# coqui-v1_0-linear.net
KiCad netlist of a schematic drawn in EAGLE
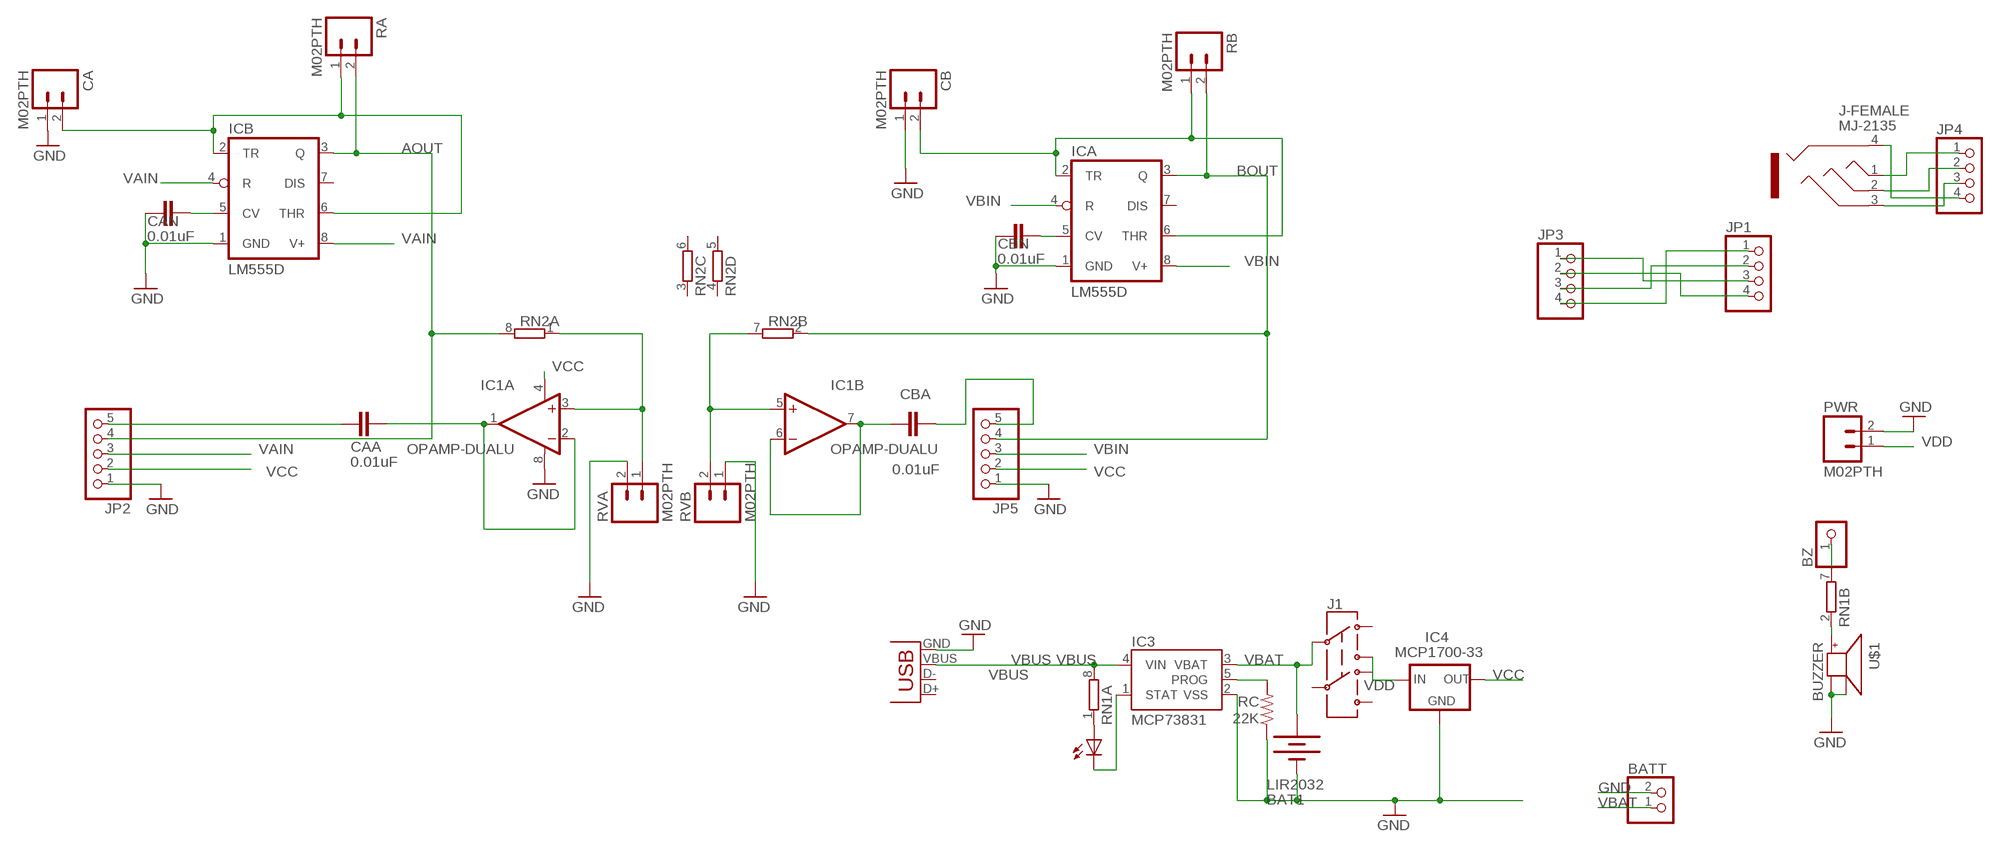
[diagram p0: schematic, sheet 1]

(export (version "E")
  (design (tool "Eeschema 10.0.6"))
  (components
    (comp (ref "BAT1")
      (value "LIR2032")
      (footprint "eagle-import:BATTCOM_20MM_PTH_SMT")
      (libsource (lib "eagle-import") (part "BATTERYBATTCOM_20MM_PTH_SMT"))
    )
    (comp (ref "BATT")
      (value "JST_2PIN-SMT-RA")
      (footprint "eagle-import:JST-PH-2-SMT-RA")
      (libsource (lib "eagle-import") (part "JST_2PIN-SMT-RA"))
    )
    (comp (ref "BZ")
      (value "PINHD-1X1")
      (footprint "eagle-import:1X01")
      (libsource (lib "eagle-import") (part "PINHD-1X1"))
    )
    (comp (ref "CA")
      (value "M02PTH")
      (footprint "eagle-import:1X02")
      (libsource (lib "eagle-import") (part "M02PTH"))
    )
    (comp (ref "CAA")
      (value "0.01uF")
      (footprint "eagle-import:C0805@1")
      (libsource (lib "eagle-import") (part "C-EUC0805"))
    )
    (comp (ref "CAN")
      (value "0.01uF")
      (footprint "eagle-import:C0805@1")
      (libsource (lib "eagle-import") (part "C-EUC0805"))
    )
    (comp (ref "CB")
      (value "M02PTH")
      (footprint "eagle-import:1X02")
      (libsource (lib "eagle-import") (part "M02PTH"))
    )
    (comp (ref "CBA")
      (value "0.01uF")
      (footprint "eagle-import:C0805@1")
      (libsource (lib "eagle-import") (part "C-EUC0805"))
    )
    (comp (ref "CBN")
      (value "0.01uF")
      (footprint "eagle-import:C0805@1")
      (libsource (lib "eagle-import") (part "C-EUC0805"))
    )
    (comp (ref "CHG")
      (value "0805")
      (footprint "eagle-import:CHIPLED_0805")
      (libsource (lib "eagle-import") (part "LEDCHIPLED_0805"))
    )
    (comp (ref "IC1")
      (value "OPAMP-DUALU")
      (footprint "eagle-import:SO08")
      (libsource (lib "eagle-import") (part "OPAMP-DUALU"))
    )
    (comp (ref "IC3")
      (value "MCP73831")
      (footprint "eagle-import:SOT23-5")
      (libsource (lib "eagle-import") (part "MCP73831"))
    )
    (comp (ref "IC4")
      (value "MCP1700-33")
      (footprint "eagle-import:SOT89")
      (libsource (lib "eagle-import") (part "MCP1700SOT89"))
    )
    (comp (ref "ICA")
      (value "LM555D")
      (footprint "eagle-import:SO08")
      (libsource (lib "eagle-import") (part "555DLM"))
    )
    (comp (ref "ICB")
      (value "LM555D")
      (footprint "eagle-import:SO08")
      (libsource (lib "eagle-import") (part "555DLM"))
    )
    (comp (ref "J-FEMALE")
      (value "MJ-2135")
      (footprint "eagle-import:MJ-2135")
      (libsource (lib "eagle-import") (part "MJ-2135"))
    )
    (comp (ref "J1")
      (value "AYZ0202")
      (footprint "eagle-import:AYZ0202")
      (libsource (lib "eagle-import") (part "AYZ0202"))
    )
    (comp (ref "JP1")
      (value "PINHD-1X4/90")
      (footprint "eagle-import:1X04_90")
      (libsource (lib "eagle-import") (part "trrs-dwb_PINHD-1X4/90"))
    )
    (comp (ref "JP2")
      (value "PINHD-1X5")
      (footprint "eagle-import:1X05")
      (libsource (lib "eagle-import") (part "PINHD-1X5"))
    )
    (comp (ref "JP3")
      (value "PINHD-1X4")
      (footprint "eagle-import:1X04")
      (libsource (lib "eagle-import") (part "PINHD-1X4"))
    )
    (comp (ref "JP4")
      (value "PINHD-1X4")
      (footprint "eagle-import:1X04")
      (libsource (lib "eagle-import") (part "PINHD-1X4"))
    )
    (comp (ref "JP5")
      (value "PINHD-1X5")
      (footprint "eagle-import:1X05")
      (libsource (lib "eagle-import") (part "PINHD-1X5"))
    )
    (comp (ref "PWR")
      (value "M02PTH")
      (footprint "eagle-import:1X02")
      (libsource (lib "eagle-import") (part "M02PTH"))
    )
    (comp (ref "RA")
      (value "M02PTH")
      (footprint "eagle-import:1X02")
      (libsource (lib "eagle-import") (part "M02PTH"))
    )
    (comp (ref "RB")
      (value "M02PTH")
      (footprint "eagle-import:1X02")
      (libsource (lib "eagle-import") (part "M02PTH"))
    )
    (comp (ref "RC")
      (value "22K")
      (footprint "eagle-import:R0805")
      (libsource (lib "eagle-import") (part "R-US_R0805"))
    )
    (comp (ref "RN1")
      (value "4R-NEXB38V")
      (footprint "eagle-import:EXB38V")
      (libsource (lib "eagle-import") (part "4R-NEXB38V"))
    )
    (comp (ref "RN2")
      (value "4R-NEXB38V")
      (footprint "eagle-import:EXB38V")
      (libsource (lib "eagle-import") (part "4R-NEXB38V"))
    )
    (comp (ref "RVA")
      (value "M02PTH")
      (footprint "eagle-import:1X02")
      (libsource (lib "eagle-import") (part "M02PTH"))
    )
    (comp (ref "RVB")
      (value "M02PTH")
      (footprint "eagle-import:1X02")
      (libsource (lib "eagle-import") (part "M02PTH"))
    )
    (comp (ref "U$1")
      (value "BUZZER")
      (footprint "eagle-import:SMT-8585-BUZZER")
      (libsource (lib "eagle-import") (part "BUZZER"))
    )
    (comp (ref "X1")
      (value "USBSMD")
      (footprint "eagle-import:USB-MINIB")
      (libsource (lib "eagle-import") (part "USBSMD"))
    )
  )
  (nets
    (net (code "1") (name "/AOUT") (class "Default")
      (node (ref "ICB") (pin "3") (pinfunction "Q_3") (pintype "output"))
      (node (ref "JP2") (pin "4") (pinfunction "4_4") (pintype "passive"))
      (node (ref "RA") (pin "2") (pinfunction "2_2") (pintype "passive"))
      (node (ref "RN2") (pin "8") (pinfunction "2_8") (pintype "passive"))
    )
    (net (code "2") (name "/BOUT") (class "Default")
      (node (ref "ICA") (pin "3") (pinfunction "Q_3") (pintype "output"))
      (node (ref "JP5") (pin "4") (pinfunction "4_4") (pintype "passive"))
      (node (ref "RB") (pin "2") (pinfunction "2_2") (pintype "passive"))
      (node (ref "RN2") (pin "2") (pinfunction "1_2") (pintype "passive"))
    )
    (net (code "3") (name "/N$23") (class "Default")
      (node (ref "IC1") (pin "3") (pinfunction "+IN_3") (pintype "input"))
      (node (ref "IC1") (pin "5") (pinfunction "+IN_5") (pintype "input"))
      (node (ref "RN2") (pin "1") (pinfunction "1_1") (pintype "passive"))
      (node (ref "RN2") (pin "7") (pinfunction "2_7") (pintype "passive"))
      (node (ref "RVA") (pin "1") (pinfunction "1_1") (pintype "passive"))
      (node (ref "RVB") (pin "2") (pinfunction "2_2") (pintype "passive"))
    )
    (net (code "4") (name "/VAIN") (class "Default")
      (node (ref "ICB") (pin "4") (pinfunction "R_4") (pintype "input"))
      (node (ref "ICB") (pin "8") (pinfunction "V+_8") (pintype "power_in"))
      (node (ref "JP2") (pin "3") (pinfunction "3_3") (pintype "passive"))
    )
    (net (code "5") (name "/VBAT") (class "Default")
      (node (ref "BAT1") (pin "P$2") (pinfunction "+_P$2") (pintype "power_in"))
      (node (ref "BATT") (pin "1") (pinfunction "2_1") (pintype "passive"))
      (node (ref "IC3") (pin "3") (pinfunction "VBAT_3") (pintype "power_in"))
      (node (ref "J1") (pin "2") (pinfunction "2_2") (pintype "bidirectional"))
    )
    (net (code "6") (name "/VBIN") (class "Default")
      (node (ref "ICA") (pin "4") (pinfunction "R_4") (pintype "input"))
      (node (ref "ICA") (pin "8") (pinfunction "V+_8") (pintype "power_in"))
      (node (ref "JP5") (pin "3") (pinfunction "3_3") (pintype "passive"))
    )
    (net (code "7") (name "/VBUS") (class "Default")
      (node (ref "IC3") (pin "4") (pinfunction "VIN_4") (pintype "power_in"))
      (node (ref "RN1") (pin "8") (pinfunction "2_8") (pintype "passive"))
      (node (ref "X1") (pin "VBUS") (pinfunction "VBUS_VBUS") (pintype "bidirectional"))
    )
    (net (code "8") (name "/VCC") (class "Default")
      (node (ref "IC1") (pin "4") (pinfunction "V-_4") (pintype "power_in"))
      (node (ref "IC4") (pin "3") (pinfunction "OUT_3") (pintype "passive"))
      (node (ref "JP2") (pin "2") (pinfunction "2_2") (pintype "passive"))
      (node (ref "JP5") (pin "2") (pinfunction "2_2") (pintype "passive"))
    )
    (net (code "9") (name "/VDD") (class "Default")
      (node (ref "IC4") (pin "2") (pinfunction "IN_2") (pintype "input"))
      (node (ref "J1") (pin "1") (pinfunction "3_1") (pintype "bidirectional"))
      (node (ref "PWR") (pin "1") (pinfunction "1_1") (pintype "passive"))
    )
    (net (code "10") (name "GND") (class "Default")
      (node (ref "BAT1") (pin "P$1") (pinfunction "-_P$1") (pintype "power_in"))
      (node (ref "BATT") (pin "2") (pinfunction "1_2") (pintype "passive"))
      (node (ref "CA") (pin "1") (pinfunction "1_1") (pintype "passive"))
      (node (ref "CAN") (pin "1") (pinfunction "1_1") (pintype "passive"))
      (node (ref "CB") (pin "1") (pinfunction "1_1") (pintype "passive"))
      (node (ref "CBN") (pin "1") (pinfunction "1_1") (pintype "passive"))
      (node (ref "IC1") (pin "8") (pinfunction "V+_8") (pintype "power_in"))
      (node (ref "IC3") (pin "2") (pinfunction "VSS_2") (pintype "power_in"))
      (node (ref "IC4") (pin "1") (pinfunction "GND_1") (pintype "input"))
      (node (ref "ICA") (pin "1") (pinfunction "GND_1") (pintype "power_in"))
      (node (ref "ICB") (pin "1") (pinfunction "GND_1") (pintype "power_in"))
      (node (ref "JP2") (pin "1") (pinfunction "1_1") (pintype "passive"))
      (node (ref "JP5") (pin "1") (pinfunction "1_1") (pintype "passive"))
      (node (ref "PWR") (pin "2") (pinfunction "2_2") (pintype "passive"))
      (node (ref "RC") (pin "1") (pinfunction "1_1") (pintype "passive"))
      (node (ref "RVA") (pin "2") (pinfunction "2_2") (pintype "passive"))
      (node (ref "RVB") (pin "1") (pinfunction "1_1") (pintype "passive"))
      (node (ref "U$1") (pin "-") (pinfunction "-_-") (pintype "passive"))
      (node (ref "U$1") (pin "A-") (pinfunction "A-_A-") (pintype "passive"))
      (node (ref "X1") (pin "GND") (pinfunction "GND_GND") (pintype "bidirectional"))
    )
    (net (code "11") (name "Net-(CAA-Pad1)") (class "Default")
      (node (ref "CAA") (pin "1") (pinfunction "1_1") (pintype "passive"))
      (node (ref "JP2") (pin "5") (pinfunction "5_5") (pintype "passive"))
    )
    (net (code "12") (name "Net-(CBA-Pad2)") (class "Default")
      (node (ref "CBA") (pin "2") (pinfunction "2_2") (pintype "passive"))
      (node (ref "JP5") (pin "5") (pinfunction "5_5") (pintype "passive"))
    )
    (net (code "13") (name "Net-(CHG-PadA)") (class "Default")
      (node (ref "CHG") (pin "A") (pinfunction "A_A") (pintype "passive"))
      (node (ref "RN1") (pin "1") (pinfunction "1_1") (pintype "passive"))
    )
    (net (code "14") (name "Net-(IC1A--IN)") (class "Default")
      (node (ref "CAA") (pin "2") (pinfunction "2_2") (pintype "passive"))
      (node (ref "IC1") (pin "1") (pinfunction "OUT_1") (pintype "output"))
      (node (ref "IC1") (pin "2") (pinfunction "-IN_2") (pintype "input"))
    )
    (net (code "15") (name "Net-(IC1B--IN)") (class "Default")
      (node (ref "CBA") (pin "1") (pinfunction "1_1") (pintype "passive"))
      (node (ref "IC1") (pin "6") (pinfunction "-IN_6") (pintype "input"))
      (node (ref "IC1") (pin "7") (pinfunction "OUT_7") (pintype "output"))
    )
    (net (code "16") (name "Net-(IC3-PROG)") (class "Default")
      (node (ref "IC3") (pin "5") (pinfunction "PROG_5") (pintype "input"))
      (node (ref "RC") (pin "2") (pinfunction "2_2") (pintype "passive"))
    )
    (net (code "17") (name "Net-(IC3-STAT)") (class "Default")
      (node (ref "CHG") (pin "C") (pinfunction "C_C") (pintype "passive"))
      (node (ref "IC3") (pin "1") (pinfunction "STAT_1") (pintype "output"))
    )
    (net (code "18") (name "Net-(ICA-CV)") (class "Default")
      (node (ref "CBN") (pin "2") (pinfunction "2_2") (pintype "passive"))
      (node (ref "ICA") (pin "5") (pinfunction "CV_5") (pintype "input"))
    )
    (net (code "19") (name "Net-(ICA-THR)") (class "Default")
      (node (ref "CB") (pin "2") (pinfunction "2_2") (pintype "passive"))
      (node (ref "ICA") (pin "2") (pinfunction "TR_2") (pintype "input"))
      (node (ref "ICA") (pin "6") (pinfunction "THR_6") (pintype "input"))
      (node (ref "RB") (pin "1") (pinfunction "1_1") (pintype "passive"))
    )
    (net (code "20") (name "Net-(ICB-CV)") (class "Default")
      (node (ref "CAN") (pin "2") (pinfunction "2_2") (pintype "passive"))
      (node (ref "ICB") (pin "5") (pinfunction "CV_5") (pintype "input"))
    )
    (net (code "21") (name "Net-(ICB-THR)") (class "Default")
      (node (ref "CA") (pin "2") (pinfunction "2_2") (pintype "passive"))
      (node (ref "ICB") (pin "2") (pinfunction "TR_2") (pintype "input"))
      (node (ref "ICB") (pin "6") (pinfunction "THR_6") (pintype "input"))
      (node (ref "RA") (pin "1") (pinfunction "1_1") (pintype "passive"))
    )
    (net (code "22") (name "Net-(J-FEMALE-Pad1)") (class "Default")
      (node (ref "J-FEMALE") (pin "1") (pinfunction "1_1") (pintype "passive"))
      (node (ref "JP4") (pin "1") (pinfunction "1_1") (pintype "passive"))
    )
    (net (code "23") (name "Net-(J-FEMALE-Pad2)") (class "Default")
      (node (ref "J-FEMALE") (pin "2") (pinfunction "2_2") (pintype "passive"))
      (node (ref "JP4") (pin "2") (pinfunction "2_2") (pintype "passive"))
    )
    (net (code "24") (name "Net-(J-FEMALE-Pad3)") (class "Default")
      (node (ref "J-FEMALE") (pin "3") (pinfunction "3_3") (pintype "passive"))
      (node (ref "JP4") (pin "3") (pinfunction "3_3") (pintype "passive"))
    )
    (net (code "25") (name "Net-(J-FEMALE-Pad4)") (class "Default")
      (node (ref "J-FEMALE") (pin "4") (pinfunction "4_4") (pintype "passive"))
      (node (ref "JP4") (pin "4") (pinfunction "4_4") (pintype "passive"))
    )
    (net (code "26") (name "Net-(JP1-Pad1)") (class "Default")
      (node (ref "JP1") (pin "1") (pinfunction "1_1") (pintype "passive"))
      (node (ref "JP3") (pin "4") (pinfunction "4_4") (pintype "passive"))
    )
    (net (code "27") (name "Net-(JP1-Pad2)") (class "Default")
      (node (ref "JP1") (pin "2") (pinfunction "2_2") (pintype "passive"))
      (node (ref "JP3") (pin "3") (pinfunction "3_3") (pintype "passive"))
    )
    (net (code "28") (name "Net-(JP1-Pad3)") (class "Default")
      (node (ref "JP1") (pin "3") (pinfunction "3_3") (pintype "passive"))
      (node (ref "JP3") (pin "1") (pinfunction "1_1") (pintype "passive"))
    )
    (net (code "29") (name "Net-(JP1-Pad4)") (class "Default")
      (node (ref "JP1") (pin "4") (pinfunction "4_4") (pintype "passive"))
      (node (ref "JP3") (pin "2") (pinfunction "2_2") (pintype "passive"))
    )
    (net (code "30") (name "Net-(RN1B-1)") (class "Default")
      (node (ref "RN1") (pin "2") (pinfunction "1_2") (pintype "passive"))
      (node (ref "U$1") (pin "+") (pinfunction "+_+") (pintype "passive"))
    )
    (net (code "31") (name "Net-(RN1B-2)") (class "Default")
      (node (ref "BZ") (pin "1") (pinfunction "1_1") (pintype "passive"))
      (node (ref "RN1") (pin "7") (pinfunction "2_7") (pintype "passive"))
    )
    (net (code "32") (name "unconnected-(ICA-DIS-Pad7)") (class "Default")
      (node (ref "ICA") (pin "7") (pinfunction "DIS_7") (pintype "input"))
    )
    (net (code "33") (name "unconnected-(ICB-DIS-Pad7)") (class "Default")
      (node (ref "ICB") (pin "7") (pinfunction "DIS_7") (pintype "input"))
    )
    (net (code "34") (name "unconnected-(J1-1-Pad3)") (class "Default")
      (node (ref "J1") (pin "3") (pinfunction "1_3") (pintype "bidirectional"))
    )
    (net (code "35") (name "unconnected-(J1-4-Pad6)") (class "Default")
      (node (ref "J1") (pin "6") (pinfunction "4_6") (pintype "bidirectional"))
    )
    (net (code "36") (name "unconnected-(J1-6-Pad4)") (class "Default")
      (node (ref "J1") (pin "4") (pinfunction "6_4") (pintype "bidirectional"))
    )
    (net (code "37") (name "unconnected-(J1-Pad5)") (class "Default")
      (node (ref "J1") (pin "5") (pinfunction "5_5") (pintype "bidirectional"))
    )
    (net (code "38") (name "unconnected-(RN2C-1-Pad3)") (class "Default")
      (node (ref "RN2") (pin "3") (pinfunction "1_3") (pintype "passive"))
    )
    (net (code "39") (name "unconnected-(RN2C-2-Pad6)") (class "Default")
      (node (ref "RN2") (pin "6") (pinfunction "2_6") (pintype "passive"))
    )
    (net (code "40") (name "unconnected-(RN2D-1-Pad4)") (class "Default")
      (node (ref "RN2") (pin "4") (pinfunction "1_4") (pintype "passive"))
    )
    (net (code "41") (name "unconnected-(RN2D-2-Pad5)") (class "Default")
      (node (ref "RN2") (pin "5") (pinfunction "2_5") (pintype "passive"))
    )
    (net (code "42") (name "unconnected-(X1-PadD+)") (class "Default")
      (node (ref "X1") (pin "D+") (pinfunction "D+_D+") (pintype "bidirectional"))
    )
    (net (code "43") (name "unconnected-(X1-PadD-)") (class "Default")
      (node (ref "X1") (pin "D-") (pinfunction "D-_D-") (pintype "bidirectional"))
    )
  )
)
